# Integrators.net
KiCad netlist of a schematic drawn in Altium Designer
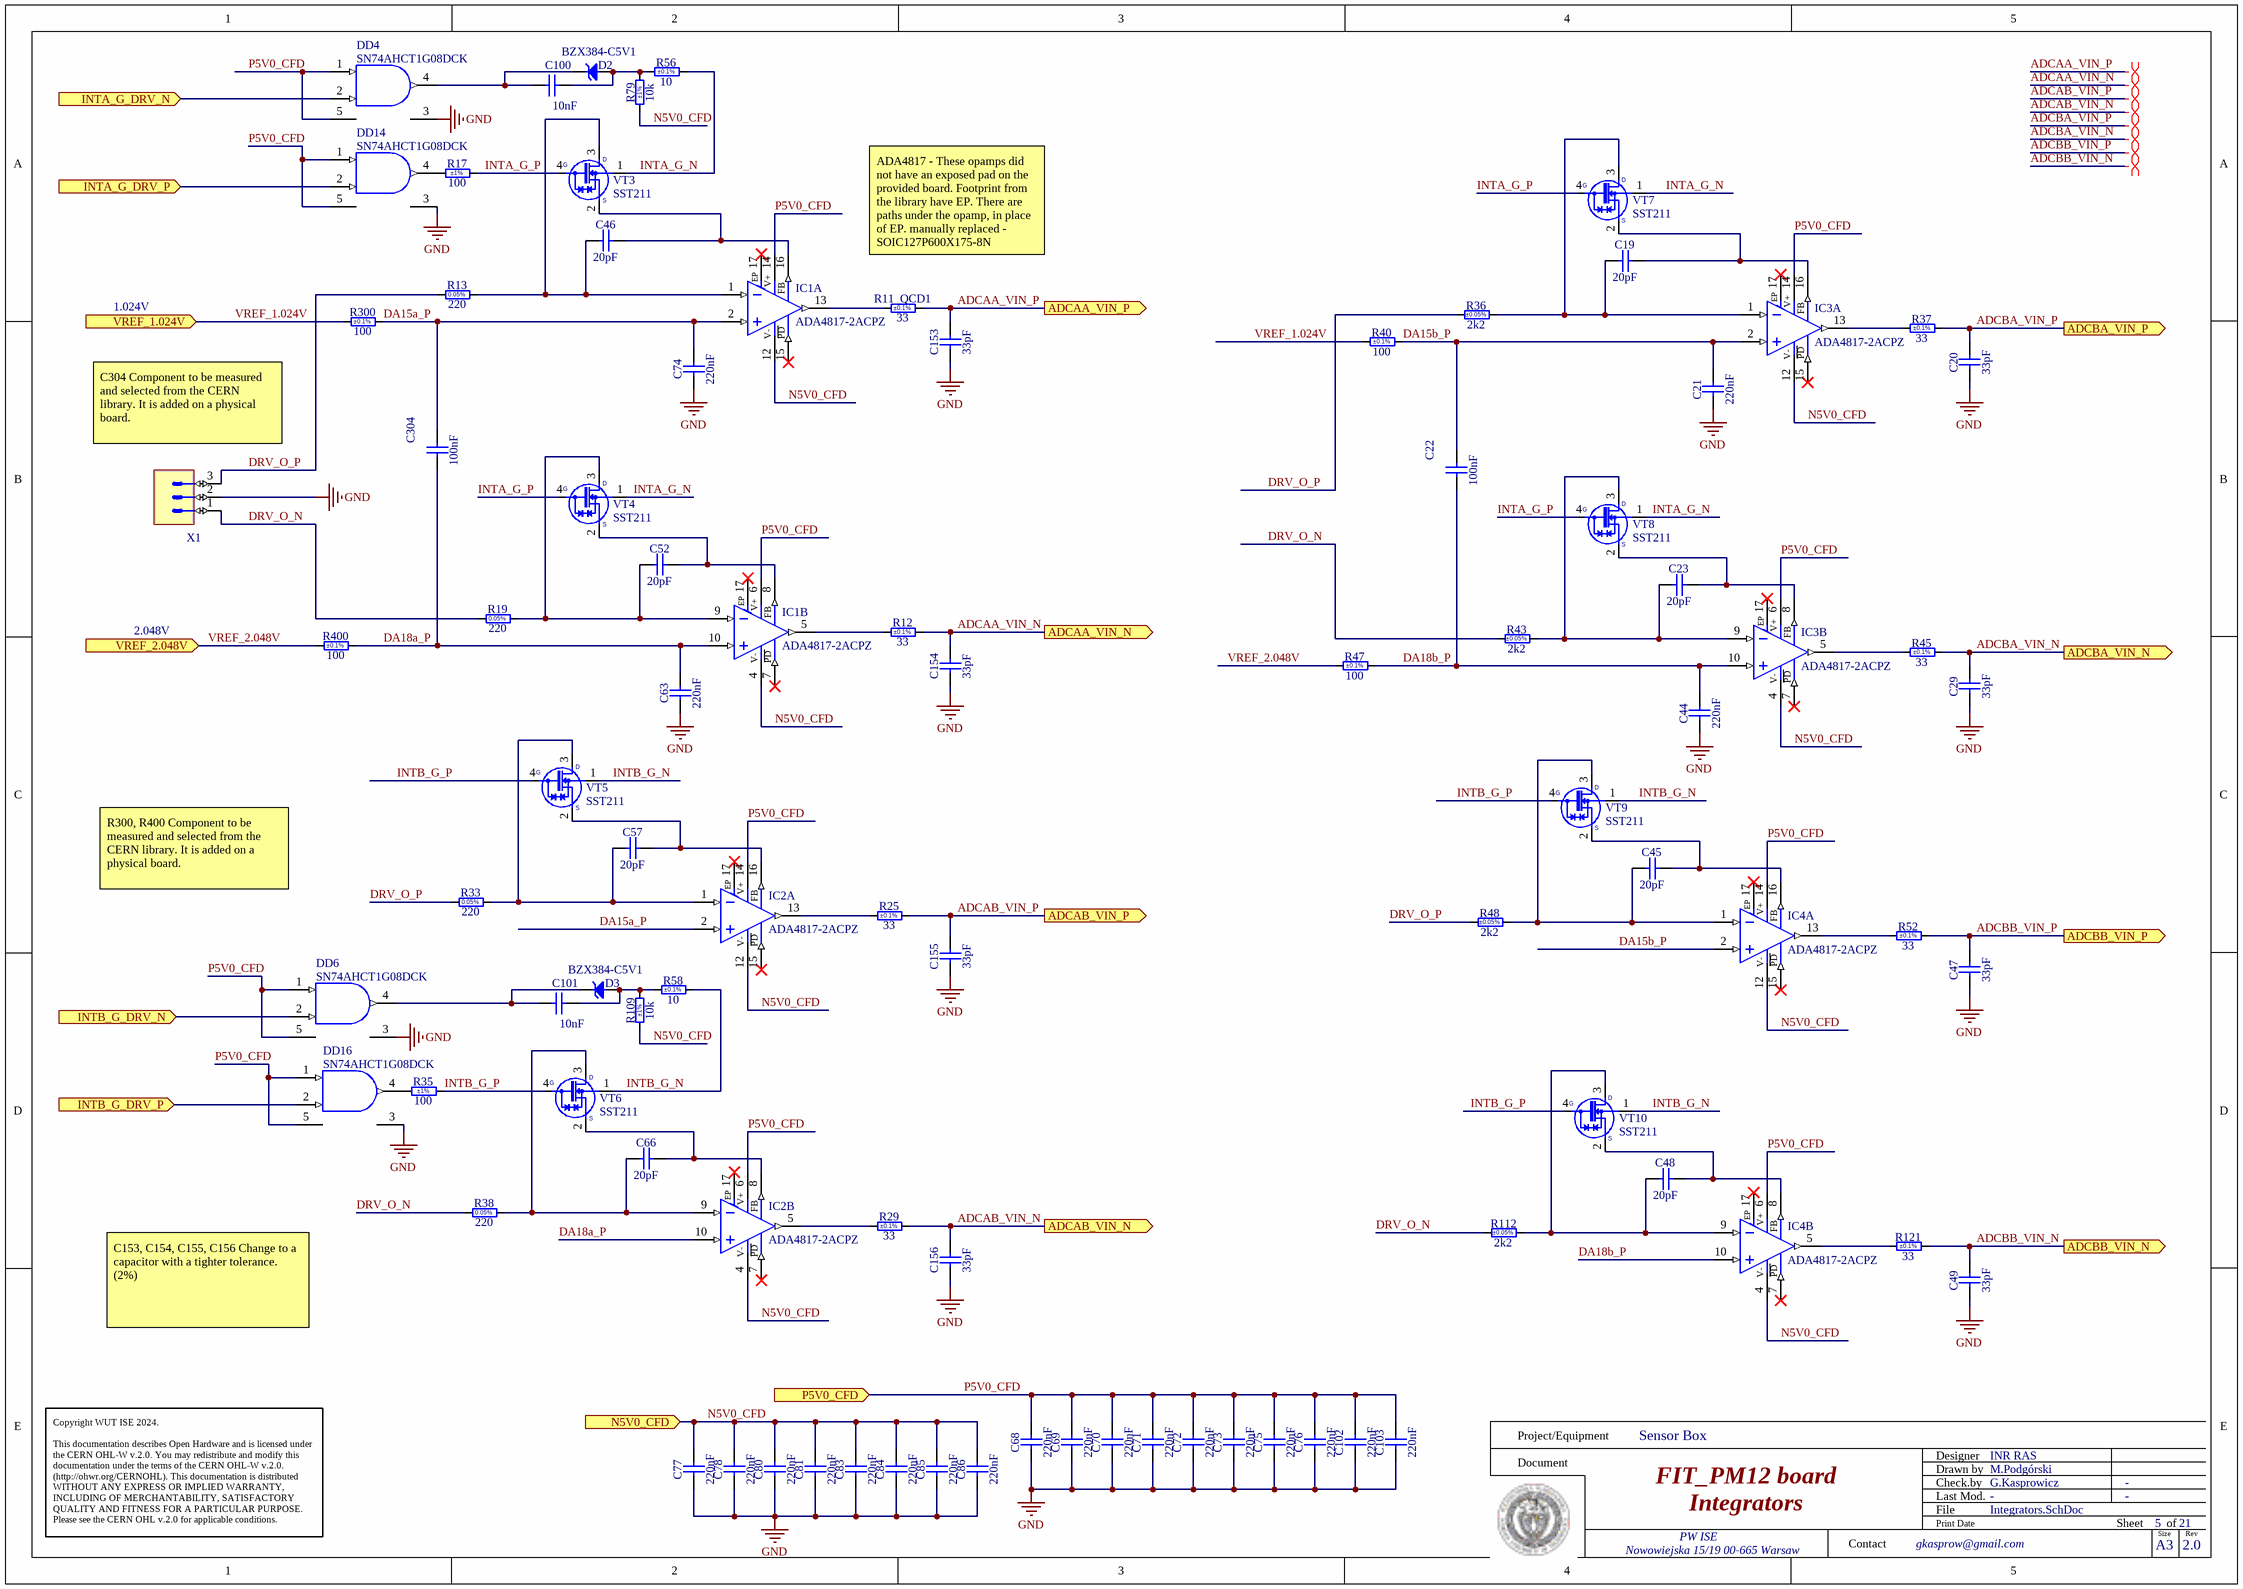
[diagram p0: Integrators.SchDoc]

(export (version "E")
  (design (tool "Eeschema 10.0.6"))
  (components
    (comp (ref "C19")
      (value "20pF")
      (footprint "CAPC2012X135N")
      (description "Non-polarised capacitor")
      (fields
        (field (name "PART NUMBER") "CC0805_20PF_50V_2%_C0G")
        (field (name "VOLTAGE") "50V")
        (field (name "AUTHOR") "CERN DEM HF")
      )
      (libsource (lib "Capacitors") (part "Capacitor - non polarized"))
    )
    (comp (ref "C20")
      (value "33pF")
      (footprint "CAPC1608X87N")
      (description "Non-polarised capacitor")
      (fields
        (field (name "PART NUMBER") "CC0603_33PF_50V_5%_NP0")
        (field (name "VOLTAGE") "50V")
        (field (name "AUTHOR") "CERN DEM JLC")
      )
      (libsource (lib "Capacitors") (part "Capacitor - non polarized"))
    )
    (comp (ref "C21")
      (value "220nF")
      (footprint "CAPC1005X55N")
      (description "Non-polarised capacitor")
      (fields
        (field (name "PART NUMBER") "CC0402_220NF_16V_10%_X7R")
        (field (name "VOLTAGE") "16V")
        (field (name "AUTHOR") "CERN DEM JLC")
      )
      (libsource (lib "Capacitors") (part "Capacitor - non polarized"))
    )
    (comp (ref "C22")
      (value "100nF")
      (footprint "CAPC2012X88N")
      (description "Non-polarised capacitor")
      (fields
        (field (name "PART NUMBER") "CC0805_100NF_50V_1%_NP0")
        (field (name "VOLTAGE") "50V")
        (field (name "AUTHOR") "CERN DEM HF")
      )
      (libsource (lib "Capacitors") (part "Capacitor - non polarized"))
    )
    (comp (ref "C23")
      (value "20pF")
      (footprint "CAPC2012X135N")
      (description "Non-polarised capacitor")
      (fields
        (field (name "PART NUMBER") "CC0805_20PF_50V_2%_C0G")
        (field (name "VOLTAGE") "50V")
        (field (name "AUTHOR") "CERN DEM HF")
      )
      (libsource (lib "Capacitors") (part "Capacitor - non polarized"))
    )
    (comp (ref "C29")
      (value "33pF")
      (footprint "CAPC1608X87N")
      (description "Non-polarised capacitor")
      (fields
        (field (name "PART NUMBER") "CC0603_33PF_50V_5%_NP0")
        (field (name "VOLTAGE") "50V")
        (field (name "AUTHOR") "CERN DEM JLC")
      )
      (libsource (lib "Capacitors") (part "Capacitor - non polarized"))
    )
    (comp (ref "C44")
      (value "220nF")
      (footprint "CAPC1005X55N")
      (description "Non-polarised capacitor")
      (fields
        (field (name "PART NUMBER") "CC0402_220NF_16V_10%_X7R")
        (field (name "VOLTAGE") "16V")
        (field (name "AUTHOR") "CERN DEM JLC")
      )
      (libsource (lib "Capacitors") (part "Capacitor - non polarized"))
    )
    (comp (ref "C45")
      (value "20pF")
      (footprint "CAPC2012X135N")
      (description "Non-polarised capacitor")
      (fields
        (field (name "PART NUMBER") "CC0805_20PF_50V_2%_C0G")
        (field (name "VOLTAGE") "50V")
        (field (name "AUTHOR") "CERN DEM HF")
      )
      (libsource (lib "Capacitors") (part "Capacitor - non polarized"))
    )
    (comp (ref "C46")
      (value "20pF")
      (footprint "CAPC2012X135N")
      (description "Non-polarised capacitor")
      (fields
        (field (name "PART NUMBER") "CC0805_20PF_50V_2%_C0G")
        (field (name "VOLTAGE") "50V")
        (field (name "AUTHOR") "CERN DEM HF")
      )
      (libsource (lib "Capacitors") (part "Capacitor - non polarized"))
    )
    (comp (ref "C47")
      (value "33pF")
      (footprint "CAPC1608X87N")
      (description "Non-polarised capacitor")
      (fields
        (field (name "PART NUMBER") "CC0603_33PF_50V_5%_NP0")
        (field (name "VOLTAGE") "50V")
        (field (name "AUTHOR") "CERN DEM JLC")
      )
      (libsource (lib "Capacitors") (part "Capacitor - non polarized"))
    )
    (comp (ref "C48")
      (value "20pF")
      (footprint "CAPC2012X135N")
      (description "Non-polarised capacitor")
      (fields
        (field (name "PART NUMBER") "CC0805_20PF_50V_2%_C0G")
        (field (name "VOLTAGE") "50V")
        (field (name "AUTHOR") "CERN DEM HF")
      )
      (libsource (lib "Capacitors") (part "Capacitor - non polarized"))
    )
    (comp (ref "C49")
      (value "33pF")
      (footprint "CAPC1608X87N")
      (description "Non-polarised capacitor")
      (fields
        (field (name "PART NUMBER") "CC0603_33PF_50V_5%_NP0")
        (field (name "VOLTAGE") "50V")
        (field (name "AUTHOR") "CERN DEM JLC")
      )
      (libsource (lib "Capacitors") (part "Capacitor - non polarized"))
    )
    (comp (ref "C52")
      (value "20pF")
      (footprint "CAPC2012X135N")
      (description "Non-polarised capacitor")
      (fields
        (field (name "PART NUMBER") "CC0805_20PF_50V_2%_C0G")
        (field (name "VOLTAGE") "50V")
        (field (name "AUTHOR") "CERN DEM HF")
      )
      (libsource (lib "Capacitors") (part "Capacitor - non polarized"))
    )
    (comp (ref "C57")
      (value "20pF")
      (footprint "CAPC2012X135N")
      (description "Non-polarised capacitor")
      (fields
        (field (name "PART NUMBER") "CC0805_20PF_50V_2%_C0G")
        (field (name "VOLTAGE") "50V")
        (field (name "AUTHOR") "CERN DEM HF")
      )
      (libsource (lib "Capacitors") (part "Capacitor - non polarized"))
    )
    (comp (ref "C63")
      (value "220nF")
      (footprint "CAPC1005X55N")
      (description "Non-polarised capacitor")
      (fields
        (field (name "PART NUMBER") "CC0402_220NF_16V_10%_X7R")
        (field (name "VOLTAGE") "16V")
        (field (name "AUTHOR") "CERN DEM JLC")
      )
      (libsource (lib "Capacitors") (part "Capacitor - non polarized"))
    )
    (comp (ref "C66")
      (value "20pF")
      (footprint "CAPC2012X135N")
      (description "Non-polarised capacitor")
      (fields
        (field (name "PART NUMBER") "CC0805_20PF_50V_2%_C0G")
        (field (name "VOLTAGE") "50V")
        (field (name "AUTHOR") "CERN DEM HF")
      )
      (libsource (lib "Capacitors") (part "Capacitor - non polarized"))
    )
    (comp (ref "C68")
      (value "220nF")
      (footprint "CAPC1005X55N")
      (description "Non-polarised capacitor")
      (fields
        (field (name "PART NUMBER") "CC0402_220NF_16V_10%_X7R")
        (field (name "VOLTAGE") "16V")
        (field (name "AUTHOR") "CERN DEM JLC")
      )
      (libsource (lib "Capacitors") (part "Capacitor - non polarized"))
    )
    (comp (ref "C69")
      (value "220nF")
      (footprint "CAPC1005X55N")
      (description "Non-polarised capacitor")
      (fields
        (field (name "PART NUMBER") "CC0402_220NF_16V_10%_X7R")
        (field (name "VOLTAGE") "16V")
        (field (name "AUTHOR") "CERN DEM JLC")
      )
      (libsource (lib "Capacitors") (part "Capacitor - non polarized"))
    )
    (comp (ref "C70")
      (value "220nF")
      (footprint "CAPC1005X55N")
      (description "Non-polarised capacitor")
      (fields
        (field (name "PART NUMBER") "CC0402_220NF_16V_10%_X7R")
        (field (name "VOLTAGE") "16V")
        (field (name "AUTHOR") "CERN DEM JLC")
      )
      (libsource (lib "Capacitors") (part "Capacitor - non polarized"))
    )
    (comp (ref "C71")
      (value "220nF")
      (footprint "CAPC1005X55N")
      (description "Non-polarised capacitor")
      (fields
        (field (name "PART NUMBER") "CC0402_220NF_16V_10%_X7R")
        (field (name "VOLTAGE") "16V")
        (field (name "AUTHOR") "CERN DEM JLC")
      )
      (libsource (lib "Capacitors") (part "Capacitor - non polarized"))
    )
    (comp (ref "C72")
      (value "220nF")
      (footprint "CAPC1005X55N")
      (description "Non-polarised capacitor")
      (fields
        (field (name "PART NUMBER") "CC0402_220NF_16V_10%_X7R")
        (field (name "VOLTAGE") "16V")
        (field (name "AUTHOR") "CERN DEM JLC")
      )
      (libsource (lib "Capacitors") (part "Capacitor - non polarized"))
    )
    (comp (ref "C73")
      (value "220nF")
      (footprint "CAPC1005X55N")
      (description "Non-polarised capacitor")
      (fields
        (field (name "PART NUMBER") "CC0402_220NF_16V_10%_X7R")
        (field (name "VOLTAGE") "16V")
        (field (name "AUTHOR") "CERN DEM JLC")
      )
      (libsource (lib "Capacitors") (part "Capacitor - non polarized"))
    )
    (comp (ref "C74")
      (value "220nF")
      (footprint "CAPC1005X55N")
      (description "Non-polarised capacitor")
      (fields
        (field (name "PART NUMBER") "CC0402_220NF_16V_10%_X7R")
        (field (name "VOLTAGE") "16V")
        (field (name "AUTHOR") "CERN DEM JLC")
      )
      (libsource (lib "Capacitors") (part "Capacitor - non polarized"))
    )
    (comp (ref "C75")
      (value "220nF")
      (footprint "CAPC1005X55N")
      (description "Non-polarised capacitor")
      (fields
        (field (name "PART NUMBER") "CC0402_220NF_16V_10%_X7R")
        (field (name "VOLTAGE") "16V")
        (field (name "AUTHOR") "CERN DEM JLC")
      )
      (libsource (lib "Capacitors") (part "Capacitor - non polarized"))
    )
    (comp (ref "C76")
      (value "220nF")
      (footprint "CAPC1005X55N")
      (description "Non-polarised capacitor")
      (fields
        (field (name "PART NUMBER") "CC0402_220NF_16V_10%_X7R")
        (field (name "VOLTAGE") "16V")
        (field (name "AUTHOR") "CERN DEM JLC")
      )
      (libsource (lib "Capacitors") (part "Capacitor - non polarized"))
    )
    (comp (ref "C77")
      (value "220nF")
      (footprint "CAPC1005X55N")
      (description "Non-polarised capacitor")
      (fields
        (field (name "PART NUMBER") "CC0402_220NF_16V_10%_X7R")
        (field (name "VOLTAGE") "16V")
        (field (name "AUTHOR") "CERN DEM JLC")
      )
      (libsource (lib "Capacitors") (part "Capacitor - non polarized"))
    )
    (comp (ref "C78")
      (value "220nF")
      (footprint "CAPC1005X55N")
      (description "Non-polarised capacitor")
      (fields
        (field (name "PART NUMBER") "CC0402_220NF_16V_10%_X7R")
        (field (name "VOLTAGE") "16V")
        (field (name "AUTHOR") "CERN DEM JLC")
      )
      (libsource (lib "Capacitors") (part "Capacitor - non polarized"))
    )
    (comp (ref "C80")
      (value "220nF")
      (footprint "CAPC1005X55N")
      (description "Non-polarised capacitor")
      (fields
        (field (name "PART NUMBER") "CC0402_220NF_16V_10%_X7R")
        (field (name "VOLTAGE") "16V")
        (field (name "AUTHOR") "CERN DEM JLC")
      )
      (libsource (lib "Capacitors") (part "Capacitor - non polarized"))
    )
    (comp (ref "C81")
      (value "220nF")
      (footprint "CAPC1005X55N")
      (description "Non-polarised capacitor")
      (fields
        (field (name "PART NUMBER") "CC0402_220NF_16V_10%_X7R")
        (field (name "VOLTAGE") "16V")
        (field (name "AUTHOR") "CERN DEM JLC")
      )
      (libsource (lib "Capacitors") (part "Capacitor - non polarized"))
    )
    (comp (ref "C83")
      (value "220nF")
      (footprint "CAPC1005X55N")
      (description "Non-polarised capacitor")
      (fields
        (field (name "PART NUMBER") "CC0402_220NF_16V_10%_X7R")
        (field (name "VOLTAGE") "16V")
        (field (name "AUTHOR") "CERN DEM JLC")
      )
      (libsource (lib "Capacitors") (part "Capacitor - non polarized"))
    )
    (comp (ref "C84")
      (value "220nF")
      (footprint "CAPC1005X55N")
      (description "Non-polarised capacitor")
      (fields
        (field (name "PART NUMBER") "CC0402_220NF_16V_10%_X7R")
        (field (name "VOLTAGE") "16V")
        (field (name "AUTHOR") "CERN DEM JLC")
      )
      (libsource (lib "Capacitors") (part "Capacitor - non polarized"))
    )
    (comp (ref "C85")
      (value "220nF")
      (footprint "CAPC1005X55N")
      (description "Non-polarised capacitor")
      (fields
        (field (name "PART NUMBER") "CC0402_220NF_16V_10%_X7R")
        (field (name "VOLTAGE") "16V")
        (field (name "AUTHOR") "CERN DEM JLC")
      )
      (libsource (lib "Capacitors") (part "Capacitor - non polarized"))
    )
    (comp (ref "C86")
      (value "220nF")
      (footprint "CAPC1005X55N")
      (description "Non-polarised capacitor")
      (fields
        (field (name "PART NUMBER") "CC0402_220NF_16V_10%_X7R")
        (field (name "VOLTAGE") "16V")
        (field (name "AUTHOR") "CERN DEM JLC")
      )
      (libsource (lib "Capacitors") (part "Capacitor - non polarized"))
    )
    (comp (ref "C100")
      (value "10nF")
      (footprint "CAPC1005X55N")
      (description "Non-polarised capacitor")
      (fields
        (field (name "PART NUMBER") "CC0402_10NF_25V_10%_X7R")
        (field (name "VOLTAGE") "25V")
        (field (name "AUTHOR") "CERN DEM JLC")
      )
      (libsource (lib "Capacitors") (part "Capacitor - non polarized"))
    )
    (comp (ref "C101")
      (value "10nF")
      (footprint "CAPC1005X55N")
      (description "Non-polarised capacitor")
      (fields
        (field (name "PART NUMBER") "CC0402_10NF_25V_10%_X7R")
        (field (name "VOLTAGE") "25V")
        (field (name "AUTHOR") "CERN DEM JLC")
      )
      (libsource (lib "Capacitors") (part "Capacitor - non polarized"))
    )
    (comp (ref "C102")
      (value "220nF")
      (footprint "CAPC1005X55N")
      (description "Non-polarised capacitor")
      (fields
        (field (name "PART NUMBER") "CC0402_220NF_16V_10%_X7R")
        (field (name "VOLTAGE") "16V")
        (field (name "AUTHOR") "CERN DEM JLC")
      )
      (libsource (lib "Capacitors") (part "Capacitor - non polarized"))
    )
    (comp (ref "C103")
      (value "220nF")
      (footprint "CAPC1005X55N")
      (description "Non-polarised capacitor")
      (fields
        (field (name "PART NUMBER") "CC0402_220NF_16V_10%_X7R")
        (field (name "VOLTAGE") "16V")
        (field (name "AUTHOR") "CERN DEM JLC")
      )
      (libsource (lib "Capacitors") (part "Capacitor - non polarized"))
    )
    (comp (ref "C153")
      (value "33pF")
      (footprint "CAPC1608X87N")
      (description "Non-polarised capacitor")
      (fields
        (field (name "PART NUMBER") "CC0603_33PF_50V_5%_NP0")
        (field (name "VOLTAGE") "50V")
        (field (name "AUTHOR") "CERN DEM JLC")
      )
      (libsource (lib "Capacitors") (part "Capacitor - non polarized"))
    )
    (comp (ref "C154")
      (value "33pF")
      (footprint "CAPC1608X87N")
      (description "Non-polarised capacitor")
      (fields
        (field (name "PART NUMBER") "CC0603_33PF_50V_5%_NP0")
        (field (name "VOLTAGE") "50V")
        (field (name "AUTHOR") "CERN DEM JLC")
      )
      (libsource (lib "Capacitors") (part "Capacitor - non polarized"))
    )
    (comp (ref "C155")
      (value "33pF")
      (footprint "CAPC1608X87N")
      (description "Non-polarised capacitor")
      (fields
        (field (name "PART NUMBER") "CC0603_33PF_50V_5%_NP0")
        (field (name "VOLTAGE") "50V")
        (field (name "AUTHOR") "CERN DEM JLC")
      )
      (libsource (lib "Capacitors") (part "Capacitor - non polarized"))
    )
    (comp (ref "C156")
      (value "33pF")
      (footprint "CAPC1608X87N")
      (description "Non-polarised capacitor")
      (fields
        (field (name "PART NUMBER") "CC0603_33PF_50V_5%_NP0")
        (field (name "VOLTAGE") "50V")
        (field (name "AUTHOR") "CERN DEM JLC")
      )
      (libsource (lib "Capacitors") (part "Capacitor - non polarized"))
    )
    (comp (ref "C304")
      (value "100nF")
      (footprint "CAPC2012X88N")
      (description "Non-polarised capacitor")
      (fields
        (field (name "PART NUMBER") "CC0805_100NF_50V_1%_NP0")
        (field (name "VOLTAGE") "50V")
        (field (name "AUTHOR") "CERN DEM HF")
      )
      (libsource (lib "Capacitors") (part "Capacitor - non polarized"))
    )
    (comp (ref "D2")
      (value "BZX384-C5V1")
      (footprint "SOD2512X110N")
      (description "Zener Diode")
      (fields
        (field (name "VOLTAGE") "5.1V")
        (field (name "POWER") "300mW")
        (field (name "AUTHOR") "CERN DEM MR")
      )
      (libsource (lib "ICs And Semiconductors") (part "Diode Zener"))
    )
    (comp (ref "D3")
      (value "BZX384-C5V1")
      (footprint "SOD2512X110N")
      (description "Zener Diode")
      (fields
        (field (name "VOLTAGE") "5.1V")
        (field (name "POWER") "300mW")
        (field (name "AUTHOR") "CERN DEM MR")
      )
      (libsource (lib "ICs And Semiconductors") (part "Diode Zener"))
    )
    (comp (ref "DD4")
      (value "SN74AHCT1G08DCK")
      (footprint "SOT65P210X110-5N")
      (description "Single 2-Input AND Gate")
      (fields (field (name "MANUFACTURER") "TEXAS INSTRUMENTS") (field (name "AUTHOR") "CERN DEM HF"))
      (libsource (lib "ICs And Semiconductors") (part "741G08"))
    )
    (comp (ref "DD6")
      (value "SN74AHCT1G08DCK")
      (footprint "SOT65P210X110-5N")
      (description "Single 2-Input AND Gate")
      (fields (field (name "MANUFACTURER") "TEXAS INSTRUMENTS") (field (name "AUTHOR") "CERN DEM HF"))
      (libsource (lib "ICs And Semiconductors") (part "741G08"))
    )
    (comp (ref "DD14")
      (value "SN74AHCT1G08DCK")
      (footprint "SOT65P210X110-5N")
      (description "Single 2-Input AND Gate")
      (fields (field (name "MANUFACTURER") "TEXAS INSTRUMENTS") (field (name "AUTHOR") "CERN DEM HF"))
      (libsource (lib "ICs And Semiconductors") (part "741G08"))
    )
    (comp (ref "DD16")
      (value "SN74AHCT1G08DCK")
      (footprint "SOT65P210X110-5N")
      (description "Single 2-Input AND Gate")
      (fields (field (name "MANUFACTURER") "TEXAS INSTRUMENTS") (field (name "AUTHOR") "CERN DEM HF"))
      (libsource (lib "ICs And Semiconductors") (part "741G08"))
    )
    (comp (ref "IC1")
      (value "ADA4817-2ACPZ")
      (footprint "QFN65P400X400X80-17N-S240")
      (description "Dual Low Noise, 1GHz FastFEET Operational Amplifier")
      (fields
        (field (name "MANUFACTURER") "ANALOG DEVICES")
        (field (name "MANUFACTURER PART NUMBER") "ADA4817-2ACP")
        (field (name "AUTHOR") "CERN DEM BC")
      )
      (libsource (lib "ICs And Semiconductors") (part "ADA4817-2ACPZ"))
    )
    (comp (ref "IC2")
      (value "ADA4817-2ACPZ")
      (footprint "QFN65P400X400X80-17N-S240")
      (description "Dual Low Noise, 1GHz FastFEET Operational Amplifier")
      (fields
        (field (name "MANUFACTURER") "ANALOG DEVICES")
        (field (name "MANUFACTURER PART NUMBER") "ADA4817-2ACP")
        (field (name "AUTHOR") "CERN DEM BC")
      )
      (libsource (lib "ICs And Semiconductors") (part "ADA4817-2ACPZ"))
    )
    (comp (ref "IC3")
      (value "ADA4817-2ACPZ")
      (footprint "QFN65P400X400X80-17N-S240")
      (description "Dual Low Noise, 1GHz FastFEET Operational Amplifier")
      (fields
        (field (name "MANUFACTURER") "ANALOG DEVICES")
        (field (name "MANUFACTURER PART NUMBER") "ADA4817-2ACP")
        (field (name "AUTHOR") "CERN DEM BC")
      )
      (libsource (lib "ICs And Semiconductors") (part "ADA4817-2ACPZ"))
    )
    (comp (ref "IC4")
      (value "ADA4817-2ACPZ")
      (footprint "QFN65P400X400X80-17N-S240")
      (description "Dual Low Noise, 1GHz FastFEET Operational Amplifier")
      (fields
        (field (name "MANUFACTURER") "ANALOG DEVICES")
        (field (name "MANUFACTURER PART NUMBER") "ADA4817-2ACP")
        (field (name "AUTHOR") "CERN DEM BC")
      )
      (libsource (lib "ICs And Semiconductors") (part "ADA4817-2ACPZ"))
    )
    (comp (ref "R11_QCD1")
      (value "33")
      (footprint "RESC1608X64N")
      (description "Resistor - 0.1%")
      (fields
        (field (name "TOLERANCE") "±0.1%")
        (field (name "PART NUMBER") "R0603_33R_0.1%_0.1W_10PPM")
        (field (name "POWER") "0.1W")
        (field (name "AUTHOR") "CERN DEM HF")
      )
      (libsource (lib "Resistors") (part "Resistor - 0.1%"))
    )
    (comp (ref "R12")
      (value "33")
      (footprint "RESC1608X64N")
      (description "Resistor - 0.1%")
      (fields
        (field (name "TOLERANCE") "±0.1%")
        (field (name "PART NUMBER") "R0603_33R_0.1%_0.1W_10PPM")
        (field (name "POWER") "0.1W")
        (field (name "AUTHOR") "CERN DEM HF")
      )
      (libsource (lib "Resistors") (part "Resistor - 0.1%"))
    )
    (comp (ref "R13")
      (value "220")
      (footprint "RESC2012X60N")
      (description "Resistor - 0.05%")
      (fields
        (field (name "PART NUMBER") "R0805_220R_0.05%_0.125W_10PPM")
        (field (name "POWER") "0.125W")
        (field (name "AUTHOR") "CERN DEM HF")
      )
      (libsource (lib "Resistors") (part "Resistor - 0.05%"))
    )
    (comp (ref "R17")
      (value "100")
      (footprint "RESC1608X55N")
      (description "Resistor - 1%")
      (fields
        (field (name "TOLERANCE") "±1%")
        (field (name "PART NUMBER") "R0603_100R_1%_0.1W_100PPM")
        (field (name "POWER") "0.1W")
        (field (name "AUTHOR") "CERN DEM JLC")
      )
      (libsource (lib "Resistors") (part "Resistor - 1%"))
    )
    (comp (ref "R19")
      (value "220")
      (footprint "RESC2012X60N")
      (description "Resistor - 0.05%")
      (fields
        (field (name "PART NUMBER") "R0805_220R_0.05%_0.125W_10PPM")
        (field (name "POWER") "0.125W")
        (field (name "AUTHOR") "CERN DEM HF")
      )
      (libsource (lib "Resistors") (part "Resistor - 0.05%"))
    )
    (comp (ref "R25")
      (value "33")
      (footprint "RESC1608X64N")
      (description "Resistor - 0.1%")
      (fields
        (field (name "TOLERANCE") "±0.1%")
        (field (name "PART NUMBER") "R0603_33R_0.1%_0.1W_10PPM")
        (field (name "POWER") "0.1W")
        (field (name "AUTHOR") "CERN DEM HF")
      )
      (libsource (lib "Resistors") (part "Resistor - 0.1%"))
    )
    (comp (ref "R29")
      (value "33")
      (footprint "RESC1608X64N")
      (description "Resistor - 0.1%")
      (fields
        (field (name "TOLERANCE") "±0.1%")
        (field (name "PART NUMBER") "R0603_33R_0.1%_0.1W_10PPM")
        (field (name "POWER") "0.1W")
        (field (name "AUTHOR") "CERN DEM HF")
      )
      (libsource (lib "Resistors") (part "Resistor - 0.1%"))
    )
    (comp (ref "R33")
      (value "220")
      (footprint "RESC2012X60N")
      (description "Resistor - 0.05%")
      (fields
        (field (name "PART NUMBER") "R0805_220R_0.05%_0.125W_10PPM")
        (field (name "POWER") "0.125W")
        (field (name "AUTHOR") "CERN DEM HF")
      )
      (libsource (lib "Resistors") (part "Resistor - 0.05%"))
    )
    (comp (ref "R35")
      (value "100")
      (footprint "RESC1608X55N")
      (description "Resistor - 1%")
      (fields
        (field (name "TOLERANCE") "±1%")
        (field (name "PART NUMBER") "R0603_100R_1%_0.1W_100PPM")
        (field (name "POWER") "0.1W")
        (field (name "AUTHOR") "CERN DEM JLC")
      )
      (libsource (lib "Resistors") (part "Resistor - 1%"))
    )
    (comp (ref "R36")
      (value "2k2")
      (footprint "RESC2012X60N")
      (description "Resistor - 0.05%")
      (fields
        (field (name "TOLERANCE") "±0.05%")
        (field (name "PART NUMBER") "R0805_2K2_0.05%_0.125W_100PPM")
        (field (name "POWER") "0.125W")
        (field (name "AUTHOR") "CERN DEM JLC")
      )
      (libsource (lib "Resistors") (part "Resistor - 1%"))
    )
    (comp (ref "R37")
      (value "33")
      (footprint "RESC1608X64N")
      (description "Resistor - 0.1%")
      (fields
        (field (name "TOLERANCE") "±0.1%")
        (field (name "PART NUMBER") "R0603_33R_0.1%_0.1W_10PPM")
        (field (name "POWER") "0.1W")
        (field (name "AUTHOR") "CERN DEM HF")
      )
      (libsource (lib "Resistors") (part "Resistor - 0.1%"))
    )
    (comp (ref "R38")
      (value "220")
      (footprint "RESC2012X60N")
      (description "Resistor - 0.05%")
      (fields
        (field (name "PART NUMBER") "R0805_220R_0.05%_0.125W_10PPM")
        (field (name "POWER") "0.125W")
        (field (name "AUTHOR") "CERN DEM HF")
      )
      (libsource (lib "Resistors") (part "Resistor - 0.05%"))
    )
    (comp (ref "R40")
      (value "100")
      (footprint "RES_VISHAY_FCHP0402")
      (description "Resistor - 0.1%")
      (fields
        (field (name "TOLERANCE") "±0.1%")
        (field (name "PART NUMBER") "R0402_100R_0.1%_1W_25PPM_VISHAY_FCHP0402E1000BS")
        (field (name "POWER") "1W")
        (field (name "AUTHOR") "CERN DEM HF")
      )
      (libsource (lib "Resistors") (part "Resistor - 0.1%"))
    )
    (comp (ref "R43")
      (value "2k2")
      (footprint "RESC2012X60N")
      (description "Resistor - 0.05%")
      (fields
        (field (name "TOLERANCE") "±0.05%")
        (field (name "PART NUMBER") "R0805_2K2_0.05%_0.125W_100PPM")
        (field (name "POWER") "0.125W")
        (field (name "AUTHOR") "CERN DEM JLC")
      )
      (libsource (lib "Resistors") (part "Resistor - 1%"))
    )
    (comp (ref "R45")
      (value "33")
      (footprint "RESC1608X64N")
      (description "Resistor - 0.1%")
      (fields
        (field (name "TOLERANCE") "±0.1%")
        (field (name "PART NUMBER") "R0603_33R_0.1%_0.1W_10PPM")
        (field (name "POWER") "0.1W")
        (field (name "AUTHOR") "CERN DEM HF")
      )
      (libsource (lib "Resistors") (part "Resistor - 0.1%"))
    )
    (comp (ref "R47")
      (value "100")
      (footprint "RES_VISHAY_FCHP0402")
      (description "Resistor - 0.1%")
      (fields
        (field (name "TOLERANCE") "±0.1%")
        (field (name "PART NUMBER") "R0402_100R_0.1%_1W_25PPM_VISHAY_FCHP0402E1000BS")
        (field (name "POWER") "1W")
        (field (name "AUTHOR") "CERN DEM HF")
      )
      (libsource (lib "Resistors") (part "Resistor - 0.1%"))
    )
    (comp (ref "R48")
      (value "2k2")
      (footprint "RESC2012X60N")
      (description "Resistor - 0.05%")
      (fields
        (field (name "TOLERANCE") "±0.05%")
        (field (name "PART NUMBER") "R0805_2K2_0.05%_0.125W_100PPM")
        (field (name "POWER") "0.125W")
        (field (name "AUTHOR") "CERN DEM JLC")
      )
      (libsource (lib "Resistors") (part "Resistor - 1%"))
    )
    (comp (ref "R52")
      (value "33")
      (footprint "RESC1608X64N")
      (description "Resistor - 0.1%")
      (fields
        (field (name "TOLERANCE") "±0.1%")
        (field (name "PART NUMBER") "R0603_33R_0.1%_0.1W_10PPM")
        (field (name "POWER") "0.1W")
        (field (name "AUTHOR") "CERN DEM HF")
      )
      (libsource (lib "Resistors") (part "Resistor - 0.1%"))
    )
    (comp (ref "R56")
      (value "10")
      (footprint "RESC2012X60N")
      (description "Resistor - 0.1%")
      (fields
        (field (name "TOLERANCE") "±0.1%")
        (field (name "PART NUMBER") "R0805_10R_0.1%_0.1W_10PPM")
        (field (name "POWER") "0.1W")
        (field (name "AUTHOR") "CERN DEM JLC")
      )
      (libsource (lib "Resistors") (part "Resistor - 0.1%"))
    )
    (comp (ref "R58")
      (value "10")
      (footprint "RESC2012X60N")
      (description "Resistor - 0.1%")
      (fields
        (field (name "TOLERANCE") "±0.1%")
        (field (name "PART NUMBER") "R0805_10R_0.1%_0.1W_10PPM")
        (field (name "POWER") "0.1W")
        (field (name "AUTHOR") "CERN DEM JLC")
      )
      (libsource (lib "Resistors") (part "Resistor - 0.1%"))
    )
    (comp (ref "R79")
      (value "10k")
      (footprint "RESC1608X55N")
      (description "Resistor - 1%")
      (fields
        (field (name "TOLERANCE") "±1%")
        (field (name "PART NUMBER") "R0603_10K_1%_0.1W_100PPM")
        (field (name "POWER") "0.1W")
        (field (name "AUTHOR") "CERN DEM JLC")
      )
      (libsource (lib "Resistors") (part "Resistor - 1%"))
    )
    (comp (ref "R109")
      (value "10k")
      (footprint "RESC1608X55N")
      (description "Resistor - 1%")
      (fields
        (field (name "TOLERANCE") "±1%")
        (field (name "PART NUMBER") "R0603_10K_1%_0.1W_100PPM")
        (field (name "POWER") "0.1W")
        (field (name "AUTHOR") "CERN DEM JLC")
      )
      (libsource (lib "Resistors") (part "Resistor - 1%"))
    )
    (comp (ref "R112")
      (value "2k2")
      (footprint "RESC2012X60N")
      (description "Resistor - 0.05%")
      (fields
        (field (name "TOLERANCE") "±0.05%")
        (field (name "PART NUMBER") "R0805_2K2_0.05%_0.125W_100PPM")
        (field (name "POWER") "0.125W")
        (field (name "AUTHOR") "CERN DEM JLC")
      )
      (libsource (lib "Resistors") (part "Resistor - 1%"))
    )
    (comp (ref "R121")
      (value "33")
      (footprint "RESC1608X64N")
      (description "Resistor - 0.1%")
      (fields
        (field (name "TOLERANCE") "±0.1%")
        (field (name "PART NUMBER") "R0603_33R_0.1%_0.1W_10PPM")
        (field (name "POWER") "0.1W")
        (field (name "AUTHOR") "CERN DEM HF")
      )
      (libsource (lib "Resistors") (part "Resistor - 0.1%"))
    )
    (comp (ref "R300")
      (value "100")
      (footprint "RES_VISHAY_FCHP0402")
      (description "Resistor - 0.1%")
      (fields
        (field (name "TOLERANCE") "±0.1%")
        (field (name "PART NUMBER") "R0402_100R_0.1%_1W_25PPM_VISHAY_FCHP0402E1000BS")
        (field (name "POWER") "1W")
        (field (name "AUTHOR") "CERN DEM HF")
      )
      (libsource (lib "Resistors") (part "Resistor - 0.1%"))
    )
    (comp (ref "R400")
      (value "100")
      (footprint "RES_VISHAY_FCHP0402")
      (description "Resistor - 0.1%")
      (fields
        (field (name "TOLERANCE") "±0.1%")
        (field (name "PART NUMBER") "R0402_100R_0.1%_1W_25PPM_VISHAY_FCHP0402E1000BS")
        (field (name "POWER") "1W")
        (field (name "AUTHOR") "CERN DEM HF")
      )
      (libsource (lib "Resistors") (part "Resistor - 0.1%"))
    )
    (comp (ref "VT3")
      (value "SST211")
      (footprint "SOT143N")
      (description "30V, 50 mA N-Channel Enhancement Switching Transistor")
      (fields (field (name "MANUFACTURER") "Linear Systems") (field (name "AUTHOR") "CERN DEM JLC"))
      (libsource (lib "templib") (part "SST211"))
    )
    (comp (ref "VT4")
      (value "SST211")
      (footprint "SOT143N")
      (description "30V, 50 mA N-Channel Enhancement Switching Transistor")
      (fields (field (name "MANUFACTURER") "Linear Systems") (field (name "AUTHOR") "CERN DEM JLC"))
      (libsource (lib "templib") (part "SST211"))
    )
    (comp (ref "VT5")
      (value "SST211")
      (footprint "SOT143N")
      (description "30V, 50 mA N-Channel Enhancement Switching Transistor")
      (fields (field (name "MANUFACTURER") "Linear Systems") (field (name "AUTHOR") "CERN DEM JLC"))
      (libsource (lib "templib") (part "SST211"))
    )
    (comp (ref "VT6")
      (value "SST211")
      (footprint "SOT143N")
      (description "30V, 50 mA N-Channel Enhancement Switching Transistor")
      (fields (field (name "MANUFACTURER") "Linear Systems") (field (name "AUTHOR") "CERN DEM JLC"))
      (libsource (lib "templib") (part "SST211"))
    )
    (comp (ref "VT7")
      (value "SST211")
      (footprint "SOT143N")
      (description "30V, 50 mA N-Channel Enhancement Switching Transistor")
      (fields (field (name "MANUFACTURER") "Linear Systems") (field (name "AUTHOR") "CERN DEM JLC"))
      (libsource (lib "templib") (part "SST211"))
    )
    (comp (ref "VT8")
      (value "SST211")
      (footprint "SOT143N")
      (description "30V, 50 mA N-Channel Enhancement Switching Transistor")
      (fields (field (name "MANUFACTURER") "Linear Systems") (field (name "AUTHOR") "CERN DEM JLC"))
      (libsource (lib "templib") (part "SST211"))
    )
    (comp (ref "VT9")
      (value "SST211")
      (footprint "SOT143N")
      (description "30V, 50 mA N-Channel Enhancement Switching Transistor")
      (fields (field (name "MANUFACTURER") "Linear Systems") (field (name "AUTHOR") "CERN DEM JLC"))
      (libsource (lib "templib") (part "SST211"))
    )
    (comp (ref "VT10")
      (value "SST211")
      (footprint "SOT143N")
      (description "30V, 50 mA N-Channel Enhancement Switching Transistor")
      (fields (field (name "MANUFACTURER") "Linear Systems") (field (name "AUTHOR") "CERN DEM JLC"))
      (libsource (lib "templib") (part "SST211"))
    )
    (comp (ref "X1")
      (value "Header 3")
      (footprint "SAMTEC_DW-03-09-L-S-470")
      (description "Connector 3 Male")
      (fields
        (field (name "PART NUMBER") "SAMTEC_DW-03-09-L-S-470")
        (field (name "MANUFACTURER") "SAMTEC")
        (field (name "AUTHOR") "CERN DEM HF")
      )
      (libsource (lib "Connectors") (part "Connector 3 Male"))
    )
  )
  (nets
    (net (code "1") (name "/ADCAA_VIN_N") (class "Default")
      (node (ref "C154") (pin "2") (pinfunction "2_2") (pintype "passive"))
      (node (ref "R12") (pin "2") (pinfunction "2_2") (pintype "passive"))
    )
    (net (code "2") (name "/ADCAA_VIN_P") (class "Default")
      (node (ref "C153") (pin "2") (pinfunction "2_2") (pintype "passive"))
      (node (ref "R11_QCD1") (pin "2") (pinfunction "2_2") (pintype "passive"))
    )
    (net (code "3") (name "/ADCAB_VIN_N") (class "Default")
      (node (ref "C156") (pin "2") (pinfunction "2_2") (pintype "passive"))
      (node (ref "R29") (pin "2") (pinfunction "2_2") (pintype "passive"))
    )
    (net (code "4") (name "/ADCAB_VIN_P") (class "Default")
      (node (ref "C155") (pin "2") (pinfunction "2_2") (pintype "passive"))
      (node (ref "R25") (pin "2") (pinfunction "2_2") (pintype "passive"))
    )
    (net (code "5") (name "/ADCBA_VIN_N") (class "Default")
      (node (ref "C29") (pin "2") (pinfunction "2_2") (pintype "passive"))
      (node (ref "R45") (pin "2") (pinfunction "2_2") (pintype "passive"))
    )
    (net (code "6") (name "/ADCBA_VIN_P") (class "Default")
      (node (ref "C20") (pin "2") (pinfunction "2_2") (pintype "passive"))
      (node (ref "R37") (pin "2") (pinfunction "2_2") (pintype "passive"))
    )
    (net (code "7") (name "/ADCBB_VIN_N") (class "Default")
      (node (ref "C49") (pin "2") (pinfunction "2_2") (pintype "passive"))
      (node (ref "R121") (pin "2") (pinfunction "2_2") (pintype "passive"))
    )
    (net (code "8") (name "/ADCBB_VIN_P") (class "Default")
      (node (ref "C47") (pin "2") (pinfunction "2_2") (pintype "passive"))
      (node (ref "R52") (pin "2") (pinfunction "2_2") (pintype "passive"))
    )
    (net (code "9") (name "/DA15a_P") (class "Default")
      (node (ref "C304") (pin "2") (pinfunction "2_2") (pintype "passive"))
      (node (ref "C74") (pin "2") (pinfunction "2_2") (pintype "passive"))
      (node (ref "IC1") (pin "2") (pinfunction "IN+_2") (pintype "input"))
      (node (ref "IC2") (pin "2") (pinfunction "IN+_2") (pintype "input"))
      (node (ref "R300") (pin "1") (pinfunction "1_1") (pintype "passive"))
    )
    (net (code "10") (name "/DA15b_P") (class "Default")
      (node (ref "C21") (pin "2") (pinfunction "2_2") (pintype "passive"))
      (node (ref "C22") (pin "2") (pinfunction "2_2") (pintype "passive"))
      (node (ref "IC3") (pin "2") (pinfunction "IN+_2") (pintype "input"))
      (node (ref "IC4") (pin "2") (pinfunction "IN+_2") (pintype "input"))
      (node (ref "R40") (pin "1") (pinfunction "1_1") (pintype "passive"))
    )
    (net (code "11") (name "/DA18a_P") (class "Default")
      (node (ref "C304") (pin "1") (pinfunction "1_1") (pintype "passive"))
      (node (ref "C63") (pin "2") (pinfunction "2_2") (pintype "passive"))
      (node (ref "IC1") (pin "10") (pinfunction "IN+_10") (pintype "input"))
      (node (ref "IC2") (pin "10") (pinfunction "IN+_10") (pintype "input"))
      (node (ref "R400") (pin "1") (pinfunction "1_1") (pintype "passive"))
    )
    (net (code "12") (name "/DA18b_P") (class "Default")
      (node (ref "C22") (pin "1") (pinfunction "1_1") (pintype "passive"))
      (node (ref "C44") (pin "2") (pinfunction "2_2") (pintype "passive"))
      (node (ref "IC3") (pin "10") (pinfunction "IN+_10") (pintype "input"))
      (node (ref "IC4") (pin "10") (pinfunction "IN+_10") (pintype "input"))
      (node (ref "R47") (pin "1") (pinfunction "1_1") (pintype "passive"))
    )
    (net (code "13") (name "/DRV_O_N") (class "Default")
      (node (ref "R112") (pin "1") (pinfunction "1_1") (pintype "passive"))
      (node (ref "R19") (pin "1") (pinfunction "1_1") (pintype "passive"))
      (node (ref "R38") (pin "1") (pinfunction "1_1") (pintype "passive"))
      (node (ref "R43") (pin "1") (pinfunction "1_1") (pintype "passive"))
      (node (ref "X1") (pin "1") (pinfunction "1_1") (pintype "bidirectional"))
    )
    (net (code "14") (name "/DRV_O_P") (class "Default")
      (node (ref "R13") (pin "1") (pinfunction "1_1") (pintype "passive"))
      (node (ref "R33") (pin "1") (pinfunction "1_1") (pintype "passive"))
      (node (ref "R36") (pin "1") (pinfunction "1_1") (pintype "passive"))
      (node (ref "R48") (pin "1") (pinfunction "1_1") (pintype "passive"))
      (node (ref "X1") (pin "3") (pinfunction "3_3") (pintype "bidirectional"))
    )
    (net (code "15") (name "/INTA_G_DRV_N") (class "Default")
      (node (ref "DD4") (pin "2") (pinfunction "A_2") (pintype "input"))
    )
    (net (code "16") (name "/INTA_G_DRV_P") (class "Default")
      (node (ref "DD14") (pin "2") (pinfunction "A_2") (pintype "input"))
    )
    (net (code "17") (name "/INTA_G_N") (class "Default")
      (node (ref "R56") (pin "1") (pinfunction "1_1") (pintype "passive"))
      (node (ref "VT3") (pin "1") (pinfunction "SUB_1") (pintype "passive"))
      (node (ref "VT4") (pin "1") (pinfunction "SUB_1") (pintype "passive"))
      (node (ref "VT7") (pin "1") (pinfunction "SUB_1") (pintype "passive"))
      (node (ref "VT8") (pin "1") (pinfunction "SUB_1") (pintype "passive"))
    )
    (net (code "18") (name "/INTA_G_P") (class "Default")
      (node (ref "R17") (pin "2") (pinfunction "2_2") (pintype "passive"))
      (node (ref "VT3") (pin "4") (pinfunction "G_4") (pintype "passive"))
      (node (ref "VT4") (pin "4") (pinfunction "G_4") (pintype "passive"))
      (node (ref "VT7") (pin "4") (pinfunction "G_4") (pintype "passive"))
      (node (ref "VT8") (pin "4") (pinfunction "G_4") (pintype "passive"))
    )
    (net (code "19") (name "/INTB_G_DRV_N") (class "Default")
      (node (ref "DD6") (pin "2") (pinfunction "A_2") (pintype "input"))
    )
    (net (code "20") (name "/INTB_G_DRV_P") (class "Default")
      (node (ref "DD16") (pin "2") (pinfunction "A_2") (pintype "input"))
    )
    (net (code "21") (name "/INTB_G_N") (class "Default")
      (node (ref "R58") (pin "1") (pinfunction "1_1") (pintype "passive"))
      (node (ref "VT10") (pin "1") (pinfunction "SUB_1") (pintype "passive"))
      (node (ref "VT5") (pin "1") (pinfunction "SUB_1") (pintype "passive"))
      (node (ref "VT6") (pin "1") (pinfunction "SUB_1") (pintype "passive"))
      (node (ref "VT9") (pin "1") (pinfunction "SUB_1") (pintype "passive"))
    )
    (net (code "22") (name "/INTB_G_P") (class "Default")
      (node (ref "R35") (pin "2") (pinfunction "2_2") (pintype "passive"))
      (node (ref "VT10") (pin "4") (pinfunction "G_4") (pintype "passive"))
      (node (ref "VT5") (pin "4") (pinfunction "G_4") (pintype "passive"))
      (node (ref "VT6") (pin "4") (pinfunction "G_4") (pintype "passive"))
      (node (ref "VT9") (pin "4") (pinfunction "G_4") (pintype "passive"))
    )
    (net (code "23") (name "/N5V0_CFD") (class "Default")
      (node (ref "C77") (pin "2") (pinfunction "2_2") (pintype "passive"))
      (node (ref "C78") (pin "2") (pinfunction "2_2") (pintype "passive"))
      (node (ref "C80") (pin "2") (pinfunction "2_2") (pintype "passive"))
      (node (ref "C81") (pin "2") (pinfunction "2_2") (pintype "passive"))
      (node (ref "C83") (pin "2") (pinfunction "2_2") (pintype "passive"))
      (node (ref "C84") (pin "2") (pinfunction "2_2") (pintype "passive"))
      (node (ref "C85") (pin "2") (pinfunction "2_2") (pintype "passive"))
      (node (ref "C86") (pin "2") (pinfunction "2_2") (pintype "passive"))
      (node (ref "IC1") (pin "12") (pinfunction "-Vs_12") (pintype "power_in"))
      (node (ref "IC1") (pin "4") (pinfunction "-Vs_4") (pintype "power_in"))
      (node (ref "IC2") (pin "12") (pinfunction "-Vs_12") (pintype "power_in"))
      (node (ref "IC2") (pin "4") (pinfunction "-Vs_4") (pintype "power_in"))
      (node (ref "IC3") (pin "12") (pinfunction "-Vs_12") (pintype "power_in"))
      (node (ref "IC3") (pin "4") (pinfunction "-Vs_4") (pintype "power_in"))
      (node (ref "IC4") (pin "12") (pinfunction "-Vs_12") (pintype "power_in"))
      (node (ref "IC4") (pin "4") (pinfunction "-Vs_4") (pintype "power_in"))
      (node (ref "R109") (pin "1") (pinfunction "1_1") (pintype "passive"))
      (node (ref "R79") (pin "1") (pinfunction "1_1") (pintype "passive"))
    )
    (net (code "24") (name "/P5V0_CFD") (class "Default")
      (node (ref "C102") (pin "2") (pinfunction "2_2") (pintype "passive"))
      (node (ref "C103") (pin "2") (pinfunction "2_2") (pintype "passive"))
      (node (ref "C68") (pin "2") (pinfunction "2_2") (pintype "passive"))
      (node (ref "C69") (pin "2") (pinfunction "2_2") (pintype "passive"))
      (node (ref "C70") (pin "2") (pinfunction "2_2") (pintype "passive"))
      (node (ref "C71") (pin "2") (pinfunction "2_2") (pintype "passive"))
      (node (ref "C72") (pin "2") (pinfunction "2_2") (pintype "passive"))
      (node (ref "C73") (pin "2") (pinfunction "2_2") (pintype "passive"))
      (node (ref "C75") (pin "2") (pinfunction "2_2") (pintype "passive"))
      (node (ref "C76") (pin "2") (pinfunction "2_2") (pintype "passive"))
      (node (ref "DD14") (pin "1") (pinfunction "B_1") (pintype "input"))
      (node (ref "DD14") (pin "5") (pinfunction "VCC_5") (pintype "power_in"))
      (node (ref "DD16") (pin "1") (pinfunction "B_1") (pintype "input"))
      (node (ref "DD16") (pin "5") (pinfunction "VCC_5") (pintype "power_in"))
      (node (ref "DD4") (pin "1") (pinfunction "B_1") (pintype "input"))
      (node (ref "DD4") (pin "5") (pinfunction "VCC_5") (pintype "power_in"))
      (node (ref "DD6") (pin "1") (pinfunction "B_1") (pintype "input"))
      (node (ref "DD6") (pin "5") (pinfunction "VCC_5") (pintype "power_in"))
      (node (ref "IC1") (pin "14") (pinfunction "+Vs_14") (pintype "power_in"))
      (node (ref "IC1") (pin "6") (pinfunction "+Vs_6") (pintype "power_in"))
      (node (ref "IC2") (pin "14") (pinfunction "+Vs_14") (pintype "power_in"))
      (node (ref "IC2") (pin "6") (pinfunction "+Vs_6") (pintype "power_in"))
      (node (ref "IC3") (pin "14") (pinfunction "+Vs_14") (pintype "power_in"))
      (node (ref "IC3") (pin "6") (pinfunction "+Vs_6") (pintype "power_in"))
      (node (ref "IC4") (pin "14") (pinfunction "+Vs_14") (pintype "power_in"))
      (node (ref "IC4") (pin "6") (pinfunction "+Vs_6") (pintype "power_in"))
    )
    (net (code "25") (name "/VREF_1.024V") (class "Default")
      (node (ref "R300") (pin "2") (pinfunction "2_2") (pintype "passive"))
      (node (ref "R40") (pin "2") (pinfunction "2_2") (pintype "passive"))
    )
    (net (code "26") (name "/VREF_2.048V") (class "Default")
      (node (ref "R400") (pin "2") (pinfunction "2_2") (pintype "passive"))
      (node (ref "R47") (pin "2") (pinfunction "2_2") (pintype "passive"))
    )
    (net (code "27") (name "GND") (class "Default")
      (node (ref "C102") (pin "1") (pinfunction "1_1") (pintype "passive"))
      (node (ref "C103") (pin "1") (pinfunction "1_1") (pintype "passive"))
      (node (ref "C153") (pin "1") (pinfunction "1_1") (pintype "passive"))
      (node (ref "C154") (pin "1") (pinfunction "1_1") (pintype "passive"))
      (node (ref "C155") (pin "1") (pinfunction "1_1") (pintype "passive"))
      (node (ref "C156") (pin "1") (pinfunction "1_1") (pintype "passive"))
      (node (ref "C20") (pin "1") (pinfunction "1_1") (pintype "passive"))
      (node (ref "C21") (pin "1") (pinfunction "1_1") (pintype "passive"))
      (node (ref "C29") (pin "1") (pinfunction "1_1") (pintype "passive"))
      (node (ref "C44") (pin "1") (pinfunction "1_1") (pintype "passive"))
      (node (ref "C47") (pin "1") (pinfunction "1_1") (pintype "passive"))
      (node (ref "C49") (pin "1") (pinfunction "1_1") (pintype "passive"))
      (node (ref "C63") (pin "1") (pinfunction "1_1") (pintype "passive"))
      (node (ref "C68") (pin "1") (pinfunction "1_1") (pintype "passive"))
      (node (ref "C69") (pin "1") (pinfunction "1_1") (pintype "passive"))
      (node (ref "C70") (pin "1") (pinfunction "1_1") (pintype "passive"))
      (node (ref "C71") (pin "1") (pinfunction "1_1") (pintype "passive"))
      (node (ref "C72") (pin "1") (pinfunction "1_1") (pintype "passive"))
      (node (ref "C73") (pin "1") (pinfunction "1_1") (pintype "passive"))
      (node (ref "C74") (pin "1") (pinfunction "1_1") (pintype "passive"))
      (node (ref "C75") (pin "1") (pinfunction "1_1") (pintype "passive"))
      (node (ref "C76") (pin "1") (pinfunction "1_1") (pintype "passive"))
      (node (ref "C77") (pin "1") (pinfunction "1_1") (pintype "passive"))
      (node (ref "C78") (pin "1") (pinfunction "1_1") (pintype "passive"))
      (node (ref "C80") (pin "1") (pinfunction "1_1") (pintype "passive"))
      (node (ref "C81") (pin "1") (pinfunction "1_1") (pintype "passive"))
      (node (ref "C83") (pin "1") (pinfunction "1_1") (pintype "passive"))
      (node (ref "C84") (pin "1") (pinfunction "1_1") (pintype "passive"))
      (node (ref "C85") (pin "1") (pinfunction "1_1") (pintype "passive"))
      (node (ref "C86") (pin "1") (pinfunction "1_1") (pintype "passive"))
      (node (ref "DD14") (pin "3") (pinfunction "GND_3") (pintype "power_in"))
      (node (ref "DD16") (pin "3") (pinfunction "GND_3") (pintype "power_in"))
      (node (ref "DD4") (pin "3") (pinfunction "GND_3") (pintype "power_in"))
      (node (ref "DD6") (pin "3") (pinfunction "GND_3") (pintype "power_in"))
      (node (ref "X1") (pin "2") (pinfunction "2_2") (pintype "bidirectional"))
    )
    (net (code "28") (name "Net-(D2-A)") (class "Default")
      (node (ref "C100") (pin "1") (pinfunction "1_1") (pintype "passive"))
      (node (ref "D2") (pin "2") (pinfunction "A_2") (pintype "passive"))
      (node (ref "R56") (pin "2") (pinfunction "2_2") (pintype "passive"))
      (node (ref "R79") (pin "2") (pinfunction "2_2") (pintype "passive"))
    )
    (net (code "29") (name "Net-(D2-C)") (class "Default")
      (node (ref "C100") (pin "2") (pinfunction "2_2") (pintype "passive"))
      (node (ref "D2") (pin "1") (pinfunction "C_1") (pintype "passive"))
      (node (ref "DD4") (pin "4") (pinfunction "Y_4") (pintype "output"))
    )
    (net (code "30") (name "Net-(D3-A)") (class "Default")
      (node (ref "C101") (pin "1") (pinfunction "1_1") (pintype "passive"))
      (node (ref "D3") (pin "2") (pinfunction "A_2") (pintype "passive"))
      (node (ref "R109") (pin "2") (pinfunction "2_2") (pintype "passive"))
      (node (ref "R58") (pin "2") (pinfunction "2_2") (pintype "passive"))
    )
    (net (code "31") (name "Net-(D3-C)") (class "Default")
      (node (ref "C101") (pin "2") (pinfunction "2_2") (pintype "passive"))
      (node (ref "D3") (pin "1") (pinfunction "C_1") (pintype "passive"))
      (node (ref "DD6") (pin "4") (pinfunction "Y_4") (pintype "output"))
    )
    (net (code "32") (name "Net-(DD14-Y)") (class "Default")
      (node (ref "DD14") (pin "4") (pinfunction "Y_4") (pintype "output"))
      (node (ref "R17") (pin "1") (pinfunction "1_1") (pintype "passive"))
    )
    (net (code "33") (name "Net-(DD16-Y)") (class "Default")
      (node (ref "DD16") (pin "4") (pinfunction "Y_4") (pintype "output"))
      (node (ref "R35") (pin "1") (pinfunction "1_1") (pintype "passive"))
    )
    (net (code "34") (name "Net-(IC1A-FB)") (class "Default")
      (node (ref "C46") (pin "2") (pinfunction "2_2") (pintype "passive"))
      (node (ref "IC1") (pin "16") (pinfunction "FB_16") (pintype "output"))
      (node (ref "VT3") (pin "2") (pinfunction "S_2") (pintype "passive"))
    )
    (net (code "35") (name "Net-(IC1A-IN-)") (class "Default")
      (node (ref "C46") (pin "1") (pinfunction "1_1") (pintype "passive"))
      (node (ref "IC1") (pin "1") (pinfunction "IN-_1") (pintype "input"))
      (node (ref "R13") (pin "2") (pinfunction "2_2") (pintype "passive"))
      (node (ref "VT3") (pin "3") (pinfunction "D_3") (pintype "passive"))
    )
    (net (code "36") (name "Net-(IC1A-OUT)") (class "Default")
      (node (ref "IC1") (pin "13") (pinfunction "OUT_13") (pintype "output"))
      (node (ref "R11_QCD1") (pin "1") (pinfunction "1_1") (pintype "passive"))
    )
    (net (code "37") (name "Net-(IC1B-FB)") (class "Default")
      (node (ref "C52") (pin "2") (pinfunction "2_2") (pintype "passive"))
      (node (ref "IC1") (pin "8") (pinfunction "FB_8") (pintype "output"))
      (node (ref "VT4") (pin "2") (pinfunction "S_2") (pintype "passive"))
    )
    (net (code "38") (name "Net-(IC1B-IN-)") (class "Default")
      (node (ref "C52") (pin "1") (pinfunction "1_1") (pintype "passive"))
      (node (ref "IC1") (pin "9") (pinfunction "IN-_9") (pintype "input"))
      (node (ref "R19") (pin "2") (pinfunction "2_2") (pintype "passive"))
      (node (ref "VT4") (pin "3") (pinfunction "D_3") (pintype "passive"))
    )
    (net (code "39") (name "Net-(IC1B-OUT)") (class "Default")
      (node (ref "IC1") (pin "5") (pinfunction "OUT_5") (pintype "output"))
      (node (ref "R12") (pin "1") (pinfunction "1_1") (pintype "passive"))
    )
    (net (code "40") (name "Net-(IC2A-FB)") (class "Default")
      (node (ref "C57") (pin "2") (pinfunction "2_2") (pintype "passive"))
      (node (ref "IC2") (pin "16") (pinfunction "FB_16") (pintype "output"))
      (node (ref "VT5") (pin "2") (pinfunction "S_2") (pintype "passive"))
    )
    (net (code "41") (name "Net-(IC2A-IN-)") (class "Default")
      (node (ref "C57") (pin "1") (pinfunction "1_1") (pintype "passive"))
      (node (ref "IC2") (pin "1") (pinfunction "IN-_1") (pintype "input"))
      (node (ref "R33") (pin "2") (pinfunction "2_2") (pintype "passive"))
      (node (ref "VT5") (pin "3") (pinfunction "D_3") (pintype "passive"))
    )
    (net (code "42") (name "Net-(IC2A-OUT)") (class "Default")
      (node (ref "IC2") (pin "13") (pinfunction "OUT_13") (pintype "output"))
      (node (ref "R25") (pin "1") (pinfunction "1_1") (pintype "passive"))
    )
    (net (code "43") (name "Net-(IC2B-FB)") (class "Default")
      (node (ref "C66") (pin "2") (pinfunction "2_2") (pintype "passive"))
      (node (ref "IC2") (pin "8") (pinfunction "FB_8") (pintype "output"))
      (node (ref "VT6") (pin "2") (pinfunction "S_2") (pintype "passive"))
    )
    (net (code "44") (name "Net-(IC2B-IN-)") (class "Default")
      (node (ref "C66") (pin "1") (pinfunction "1_1") (pintype "passive"))
      (node (ref "IC2") (pin "9") (pinfunction "IN-_9") (pintype "input"))
      (node (ref "R38") (pin "2") (pinfunction "2_2") (pintype "passive"))
      (node (ref "VT6") (pin "3") (pinfunction "D_3") (pintype "passive"))
    )
    (net (code "45") (name "Net-(IC2B-OUT)") (class "Default")
      (node (ref "IC2") (pin "5") (pinfunction "OUT_5") (pintype "output"))
      (node (ref "R29") (pin "1") (pinfunction "1_1") (pintype "passive"))
    )
    (net (code "46") (name "Net-(IC3A-FB)") (class "Default")
      (node (ref "C19") (pin "2") (pinfunction "2_2") (pintype "passive"))
      (node (ref "IC3") (pin "16") (pinfunction "FB_16") (pintype "output"))
      (node (ref "VT7") (pin "2") (pinfunction "S_2") (pintype "passive"))
    )
    (net (code "47") (name "Net-(IC3A-IN-)") (class "Default")
      (node (ref "C19") (pin "1") (pinfunction "1_1") (pintype "passive"))
      (node (ref "IC3") (pin "1") (pinfunction "IN-_1") (pintype "input"))
      (node (ref "R36") (pin "2") (pinfunction "2_2") (pintype "passive"))
      (node (ref "VT7") (pin "3") (pinfunction "D_3") (pintype "passive"))
    )
    (net (code "48") (name "Net-(IC3A-OUT)") (class "Default")
      (node (ref "IC3") (pin "13") (pinfunction "OUT_13") (pintype "output"))
      (node (ref "R37") (pin "1") (pinfunction "1_1") (pintype "passive"))
    )
    (net (code "49") (name "Net-(IC3B-FB)") (class "Default")
      (node (ref "C23") (pin "2") (pinfunction "2_2") (pintype "passive"))
      (node (ref "IC3") (pin "8") (pinfunction "FB_8") (pintype "output"))
      (node (ref "VT8") (pin "2") (pinfunction "S_2") (pintype "passive"))
    )
    (net (code "50") (name "Net-(IC3B-IN-)") (class "Default")
      (node (ref "C23") (pin "1") (pinfunction "1_1") (pintype "passive"))
      (node (ref "IC3") (pin "9") (pinfunction "IN-_9") (pintype "input"))
      (node (ref "R43") (pin "2") (pinfunction "2_2") (pintype "passive"))
      (node (ref "VT8") (pin "3") (pinfunction "D_3") (pintype "passive"))
    )
    (net (code "51") (name "Net-(IC3B-OUT)") (class "Default")
      (node (ref "IC3") (pin "5") (pinfunction "OUT_5") (pintype "output"))
      (node (ref "R45") (pin "1") (pinfunction "1_1") (pintype "passive"))
    )
    (net (code "52") (name "Net-(IC4A-FB)") (class "Default")
      (node (ref "C45") (pin "2") (pinfunction "2_2") (pintype "passive"))
      (node (ref "IC4") (pin "16") (pinfunction "FB_16") (pintype "output"))
      (node (ref "VT9") (pin "2") (pinfunction "S_2") (pintype "passive"))
    )
    (net (code "53") (name "Net-(IC4A-IN-)") (class "Default")
      (node (ref "C45") (pin "1") (pinfunction "1_1") (pintype "passive"))
      (node (ref "IC4") (pin "1") (pinfunction "IN-_1") (pintype "input"))
      (node (ref "R48") (pin "2") (pinfunction "2_2") (pintype "passive"))
      (node (ref "VT9") (pin "3") (pinfunction "D_3") (pintype "passive"))
    )
    (net (code "54") (name "Net-(IC4A-OUT)") (class "Default")
      (node (ref "IC4") (pin "13") (pinfunction "OUT_13") (pintype "output"))
      (node (ref "R52") (pin "1") (pinfunction "1_1") (pintype "passive"))
    )
    (net (code "55") (name "Net-(IC4B-FB)") (class "Default")
      (node (ref "C48") (pin "2") (pinfunction "2_2") (pintype "passive"))
      (node (ref "IC4") (pin "8") (pinfunction "FB_8") (pintype "output"))
      (node (ref "VT10") (pin "2") (pinfunction "S_2") (pintype "passive"))
    )
    (net (code "56") (name "Net-(IC4B-IN-)") (class "Default")
      (node (ref "C48") (pin "1") (pinfunction "1_1") (pintype "passive"))
      (node (ref "IC4") (pin "9") (pinfunction "IN-_9") (pintype "input"))
      (node (ref "R112") (pin "2") (pinfunction "2_2") (pintype "passive"))
      (node (ref "VT10") (pin "3") (pinfunction "D_3") (pintype "passive"))
    )
    (net (code "57") (name "Net-(IC4B-OUT)") (class "Default")
      (node (ref "IC4") (pin "5") (pinfunction "OUT_5") (pintype "output"))
      (node (ref "R121") (pin "1") (pinfunction "1_1") (pintype "passive"))
    )
    (net (code "58") (name "unconnected-(IC1A-EP-Pad17)") (class "Default")
      (node (ref "IC1") (pin "17") (pinfunction "EP_17") (pintype "power_in+no_connect"))
    )
    (net (code "59") (name "unconnected-(IC1A-~{PD}-Pad15)") (class "Default")
      (node (ref "IC1") (pin "15") (pinfunction "~{PD}_15") (pintype "input+no_connect"))
    )
    (net (code "60") (name "unconnected-(IC1B-EP-Pad17)") (class "Default")
      (node (ref "IC1") (pin "17") (pinfunction "EP_17") (pintype "power_in+no_connect"))
    )
    (net (code "61") (name "unconnected-(IC1B-~{PD}-Pad7)") (class "Default")
      (node (ref "IC1") (pin "7") (pinfunction "~{PD}_7") (pintype "input+no_connect"))
    )
    (net (code "62") (name "unconnected-(IC2A-EP-Pad17)") (class "Default")
      (node (ref "IC2") (pin "17") (pinfunction "EP_17") (pintype "power_in+no_connect"))
    )
    (net (code "63") (name "unconnected-(IC2A-~{PD}-Pad15)") (class "Default")
      (node (ref "IC2") (pin "15") (pinfunction "~{PD}_15") (pintype "input+no_connect"))
    )
    (net (code "64") (name "unconnected-(IC2B-EP-Pad17)") (class "Default")
      (node (ref "IC2") (pin "17") (pinfunction "EP_17") (pintype "power_in+no_connect"))
    )
    (net (code "65") (name "unconnected-(IC2B-~{PD}-Pad7)") (class "Default")
      (node (ref "IC2") (pin "7") (pinfunction "~{PD}_7") (pintype "input+no_connect"))
    )
    (net (code "66") (name "unconnected-(IC3A-EP-Pad17)") (class "Default")
      (node (ref "IC3") (pin "17") (pinfunction "EP_17") (pintype "power_in+no_connect"))
    )
    (net (code "67") (name "unconnected-(IC3A-~{PD}-Pad15)") (class "Default")
      (node (ref "IC3") (pin "15") (pinfunction "~{PD}_15") (pintype "input+no_connect"))
    )
    (net (code "68") (name "unconnected-(IC3B-EP-Pad17)") (class "Default")
      (node (ref "IC3") (pin "17") (pinfunction "EP_17") (pintype "power_in+no_connect"))
    )
    (net (code "69") (name "unconnected-(IC3B-~{PD}-Pad7)") (class "Default")
      (node (ref "IC3") (pin "7") (pinfunction "~{PD}_7") (pintype "input+no_connect"))
    )
    (net (code "70") (name "unconnected-(IC4A-EP-Pad17)") (class "Default")
      (node (ref "IC4") (pin "17") (pinfunction "EP_17") (pintype "power_in+no_connect"))
    )
    (net (code "71") (name "unconnected-(IC4A-~{PD}-Pad15)") (class "Default")
      (node (ref "IC4") (pin "15") (pinfunction "~{PD}_15") (pintype "input+no_connect"))
    )
    (net (code "72") (name "unconnected-(IC4B-EP-Pad17)") (class "Default")
      (node (ref "IC4") (pin "17") (pinfunction "EP_17") (pintype "power_in+no_connect"))
    )
    (net (code "73") (name "unconnected-(IC4B-~{PD}-Pad7)") (class "Default")
      (node (ref "IC4") (pin "7") (pinfunction "~{PD}_7") (pintype "input+no_connect"))
    )
  )
)
